# final_enclosure_wiring.net
KiCad netlist of a schematic drawn in EAGLE
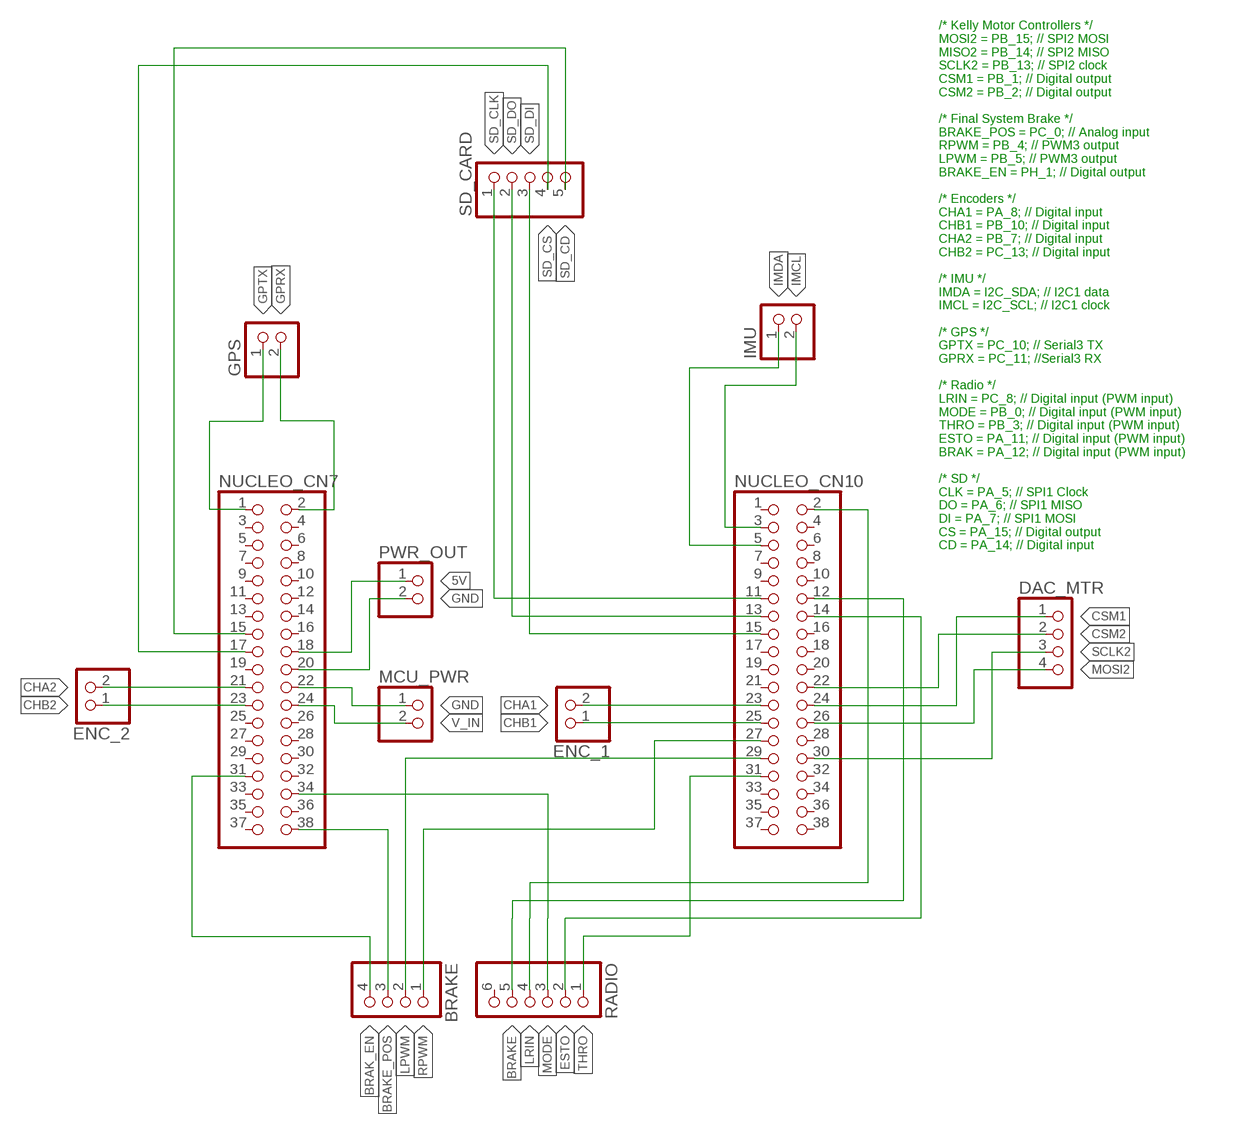
[diagram p0: schematic, sheet 1]

(export (version "E")
  (design (tool "Eeschema 10.0.6"))
  (components
    (comp (ref "BRAKE")
      (value "PINHD-1X4")
      (footprint "eagle-import:1X04")
      (libsource (lib "eagle-import") (part "PINHD-1X4"))
    )
    (comp (ref "DAC_MTR")
      (value "PINHD-1X4")
      (footprint "eagle-import:1X04")
      (libsource (lib "eagle-import") (part "PINHD-1X4"))
    )
    (comp (ref "ENC_1")
      (value "PINHD-1X2")
      (footprint "eagle-import:1X02")
      (libsource (lib "eagle-import") (part "PINHD-1X2"))
    )
    (comp (ref "ENC_2")
      (value "PINHD-1X2")
      (footprint "eagle-import:1X02")
      (libsource (lib "eagle-import") (part "PINHD-1X2"))
    )
    (comp (ref "GPS")
      (value "PINHD-1X2")
      (footprint "eagle-import:1X02")
      (libsource (lib "eagle-import") (part "PINHD-1X2"))
    )
    (comp (ref "IMU")
      (value "PINHD-1X2")
      (footprint "eagle-import:1X02")
      (libsource (lib "eagle-import") (part "PINHD-1X2"))
    )
    (comp (ref "MCU_PWR")
      (value "PINHD-1X2")
      (footprint "eagle-import:1X02")
      (libsource (lib "eagle-import") (part "PINHD-1X2"))
    )
    (comp (ref "NUCLEO_CN7")
      (value "PINHD-2X19")
      (footprint "eagle-import:2X19")
      (libsource (lib "eagle-import") (part "PINHD-2X19"))
    )
    (comp (ref "NUCLEO_CN10")
      (value "PINHD-2X19")
      (footprint "eagle-import:2X19")
      (libsource (lib "eagle-import") (part "PINHD-2X19"))
    )
    (comp (ref "PWR_OUT")
      (value "PINHD-1X2")
      (footprint "eagle-import:1X02")
      (libsource (lib "eagle-import") (part "PINHD-1X2"))
    )
    (comp (ref "RADIO")
      (value "PINHD-1X6")
      (footprint "eagle-import:1X06")
      (libsource (lib "eagle-import") (part "PINHD-1X6"))
    )
    (comp (ref "SD_CARD")
      (value "PINHD-1X5")
      (footprint "eagle-import:1X05")
      (libsource (lib "eagle-import") (part "PINHD-1X5"))
    )
  )
  (nets
    (net (code "1") (name "5V") (class "Default")
      (node (ref "NUCLEO_CN7") (pin "18") (pinfunction "18_18") (pintype "passive"))
      (node (ref "PWR_OUT") (pin "1") (pinfunction "1_1") (pintype "passive"))
    )
    (net (code "2") (name "BRAKE") (class "Default")
      (node (ref "NUCLEO_CN10") (pin "12") (pinfunction "12_12") (pintype "passive"))
      (node (ref "RADIO") (pin "5") (pinfunction "5_5") (pintype "passive"))
    )
    (net (code "3") (name "BRAKE_POS") (class "Default")
      (node (ref "BRAKE") (pin "3") (pinfunction "3_3") (pintype "passive"))
      (node (ref "NUCLEO_CN7") (pin "38") (pinfunction "38_38") (pintype "passive"))
    )
    (net (code "4") (name "BRAK_EN") (class "Default")
      (node (ref "BRAKE") (pin "4") (pinfunction "4_4") (pintype "passive"))
      (node (ref "NUCLEO_CN7") (pin "31") (pinfunction "31_31") (pintype "passive"))
    )
    (net (code "5") (name "CHA1") (class "Default")
      (node (ref "ENC_1") (pin "2") (pinfunction "2_2") (pintype "passive"))
      (node (ref "NUCLEO_CN10") (pin "23") (pinfunction "23_23") (pintype "passive"))
    )
    (net (code "6") (name "CHA2") (class "Default")
      (node (ref "ENC_2") (pin "2") (pinfunction "2_2") (pintype "passive"))
      (node (ref "NUCLEO_CN7") (pin "21") (pinfunction "21_21") (pintype "passive"))
    )
    (net (code "7") (name "CHB1") (class "Default")
      (node (ref "ENC_1") (pin "1") (pinfunction "1_1") (pintype "passive"))
      (node (ref "NUCLEO_CN10") (pin "25") (pinfunction "25_25") (pintype "passive"))
    )
    (net (code "8") (name "CHB2") (class "Default")
      (node (ref "ENC_2") (pin "1") (pinfunction "1_1") (pintype "passive"))
      (node (ref "NUCLEO_CN7") (pin "23") (pinfunction "23_23") (pintype "passive"))
    )
    (net (code "9") (name "CSM1") (class "Default")
      (node (ref "DAC_MTR") (pin "1") (pinfunction "1_1") (pintype "passive"))
      (node (ref "NUCLEO_CN10") (pin "24") (pinfunction "24_24") (pintype "passive"))
    )
    (net (code "10") (name "CSM2") (class "Default")
      (node (ref "DAC_MTR") (pin "2") (pinfunction "2_2") (pintype "passive"))
      (node (ref "NUCLEO_CN10") (pin "22") (pinfunction "22_22") (pintype "passive"))
    )
    (net (code "11") (name "ESTO") (class "Default")
      (node (ref "NUCLEO_CN10") (pin "14") (pinfunction "14_14") (pintype "passive"))
      (node (ref "RADIO") (pin "2") (pinfunction "2_2") (pintype "passive"))
    )
    (net (code "12") (name "GND") (class "Default")
      (node (ref "MCU_PWR") (pin "1") (pinfunction "1_1") (pintype "passive"))
      (node (ref "NUCLEO_CN7") (pin "20") (pinfunction "20_20") (pintype "passive"))
      (node (ref "NUCLEO_CN7") (pin "22") (pinfunction "22_22") (pintype "passive"))
      (node (ref "PWR_OUT") (pin "2") (pinfunction "2_2") (pintype "passive"))
    )
    (net (code "13") (name "GPRX") (class "Default")
      (node (ref "GPS") (pin "2") (pinfunction "2_2") (pintype "passive"))
      (node (ref "NUCLEO_CN7") (pin "2") (pinfunction "2_2") (pintype "passive"))
    )
    (net (code "14") (name "GPTX") (class "Default")
      (node (ref "GPS") (pin "1") (pinfunction "1_1") (pintype "passive"))
      (node (ref "NUCLEO_CN7") (pin "1") (pinfunction "1_1") (pintype "passive"))
    )
    (net (code "15") (name "IMCL") (class "Default")
      (node (ref "IMU") (pin "2") (pinfunction "2_2") (pintype "passive"))
      (node (ref "NUCLEO_CN10") (pin "3") (pinfunction "3_3") (pintype "passive"))
    )
    (net (code "16") (name "IMDA") (class "Default")
      (node (ref "IMU") (pin "1") (pinfunction "1_1") (pintype "passive"))
      (node (ref "NUCLEO_CN10") (pin "5") (pinfunction "5_5") (pintype "passive"))
    )
    (net (code "17") (name "LPWM") (class "Default")
      (node (ref "BRAKE") (pin "2") (pinfunction "2_2") (pintype "passive"))
      (node (ref "NUCLEO_CN10") (pin "29") (pinfunction "29_29") (pintype "passive"))
    )
    (net (code "18") (name "LRIN") (class "Default")
      (node (ref "NUCLEO_CN10") (pin "2") (pinfunction "2_2") (pintype "passive"))
      (node (ref "RADIO") (pin "4") (pinfunction "4_4") (pintype "passive"))
    )
    (net (code "19") (name "MODE") (class "Default")
      (node (ref "NUCLEO_CN7") (pin "34") (pinfunction "34_34") (pintype "passive"))
      (node (ref "RADIO") (pin "3") (pinfunction "3_3") (pintype "passive"))
    )
    (net (code "20") (name "MOSI2") (class "Default")
      (node (ref "DAC_MTR") (pin "4") (pinfunction "4_4") (pintype "passive"))
      (node (ref "NUCLEO_CN10") (pin "26") (pinfunction "26_26") (pintype "passive"))
    )
    (net (code "21") (name "RPWM") (class "Default")
      (node (ref "BRAKE") (pin "1") (pinfunction "1_1") (pintype "passive"))
      (node (ref "NUCLEO_CN10") (pin "27") (pinfunction "27_27") (pintype "passive"))
    )
    (net (code "22") (name "SCLK2") (class "Default")
      (node (ref "DAC_MTR") (pin "3") (pinfunction "3_3") (pintype "passive"))
      (node (ref "NUCLEO_CN10") (pin "30") (pinfunction "30_30") (pintype "passive"))
    )
    (net (code "23") (name "SD_CD") (class "Default")
      (node (ref "NUCLEO_CN7") (pin "15") (pinfunction "15_15") (pintype "passive"))
      (node (ref "SD_CARD") (pin "5") (pinfunction "5_5") (pintype "passive"))
    )
    (net (code "24") (name "SD_CLK") (class "Default")
      (node (ref "NUCLEO_CN10") (pin "11") (pinfunction "11_11") (pintype "passive"))
      (node (ref "SD_CARD") (pin "1") (pinfunction "1_1") (pintype "passive"))
    )
    (net (code "25") (name "SD_CS") (class "Default")
      (node (ref "NUCLEO_CN7") (pin "17") (pinfunction "17_17") (pintype "passive"))
      (node (ref "SD_CARD") (pin "4") (pinfunction "4_4") (pintype "passive"))
    )
    (net (code "26") (name "SD_DI") (class "Default")
      (node (ref "NUCLEO_CN10") (pin "15") (pinfunction "15_15") (pintype "passive"))
      (node (ref "SD_CARD") (pin "3") (pinfunction "3_3") (pintype "passive"))
    )
    (net (code "27") (name "SD_DO") (class "Default")
      (node (ref "NUCLEO_CN10") (pin "13") (pinfunction "13_13") (pintype "passive"))
      (node (ref "SD_CARD") (pin "2") (pinfunction "2_2") (pintype "passive"))
    )
    (net (code "28") (name "THRO") (class "Default")
      (node (ref "NUCLEO_CN10") (pin "31") (pinfunction "31_31") (pintype "passive"))
      (node (ref "RADIO") (pin "1") (pinfunction "1_1") (pintype "passive"))
    )
    (net (code "29") (name "V_IN") (class "Default")
      (node (ref "MCU_PWR") (pin "2") (pinfunction "2_2") (pintype "passive"))
      (node (ref "NUCLEO_CN7") (pin "24") (pinfunction "24_24") (pintype "passive"))
    )
    (net (code "30") (name "unconnected-(NUCLEO_CN7-Pad3)") (class "Default")
      (node (ref "NUCLEO_CN7") (pin "3") (pinfunction "3_3") (pintype "passive"))
    )
    (net (code "31") (name "unconnected-(NUCLEO_CN7-Pad4)") (class "Default")
      (node (ref "NUCLEO_CN7") (pin "4") (pinfunction "4_4") (pintype "passive"))
    )
    (net (code "32") (name "unconnected-(NUCLEO_CN7-Pad5)") (class "Default")
      (node (ref "NUCLEO_CN7") (pin "5") (pinfunction "5_5") (pintype "passive"))
    )
    (net (code "33") (name "unconnected-(NUCLEO_CN7-Pad6)") (class "Default")
      (node (ref "NUCLEO_CN7") (pin "6") (pinfunction "6_6") (pintype "passive"))
    )
    (net (code "34") (name "unconnected-(NUCLEO_CN7-Pad7)") (class "Default")
      (node (ref "NUCLEO_CN7") (pin "7") (pinfunction "7_7") (pintype "passive"))
    )
    (net (code "35") (name "unconnected-(NUCLEO_CN7-Pad8)") (class "Default")
      (node (ref "NUCLEO_CN7") (pin "8") (pinfunction "8_8") (pintype "passive"))
    )
    (net (code "36") (name "unconnected-(NUCLEO_CN7-Pad9)") (class "Default")
      (node (ref "NUCLEO_CN7") (pin "9") (pinfunction "9_9") (pintype "passive"))
    )
    (net (code "37") (name "unconnected-(NUCLEO_CN7-Pad10)") (class "Default")
      (node (ref "NUCLEO_CN7") (pin "10") (pinfunction "10_10") (pintype "passive"))
    )
    (net (code "38") (name "unconnected-(NUCLEO_CN7-Pad11)") (class "Default")
      (node (ref "NUCLEO_CN7") (pin "11") (pinfunction "11_11") (pintype "passive"))
    )
    (net (code "39") (name "unconnected-(NUCLEO_CN7-Pad12)") (class "Default")
      (node (ref "NUCLEO_CN7") (pin "12") (pinfunction "12_12") (pintype "passive"))
    )
    (net (code "40") (name "unconnected-(NUCLEO_CN7-Pad13)") (class "Default")
      (node (ref "NUCLEO_CN7") (pin "13") (pinfunction "13_13") (pintype "passive"))
    )
    (net (code "41") (name "unconnected-(NUCLEO_CN7-Pad14)") (class "Default")
      (node (ref "NUCLEO_CN7") (pin "14") (pinfunction "14_14") (pintype "passive"))
    )
    (net (code "42") (name "unconnected-(NUCLEO_CN7-Pad16)") (class "Default")
      (node (ref "NUCLEO_CN7") (pin "16") (pinfunction "16_16") (pintype "passive"))
    )
    (net (code "43") (name "unconnected-(NUCLEO_CN7-Pad19)") (class "Default")
      (node (ref "NUCLEO_CN7") (pin "19") (pinfunction "19_19") (pintype "passive"))
    )
    (net (code "44") (name "unconnected-(NUCLEO_CN7-Pad25)") (class "Default")
      (node (ref "NUCLEO_CN7") (pin "25") (pinfunction "25_25") (pintype "passive"))
    )
    (net (code "45") (name "unconnected-(NUCLEO_CN7-Pad26)") (class "Default")
      (node (ref "NUCLEO_CN7") (pin "26") (pinfunction "26_26") (pintype "passive"))
    )
    (net (code "46") (name "unconnected-(NUCLEO_CN7-Pad27)") (class "Default")
      (node (ref "NUCLEO_CN7") (pin "27") (pinfunction "27_27") (pintype "passive"))
    )
    (net (code "47") (name "unconnected-(NUCLEO_CN7-Pad28)") (class "Default")
      (node (ref "NUCLEO_CN7") (pin "28") (pinfunction "28_28") (pintype "passive"))
    )
    (net (code "48") (name "unconnected-(NUCLEO_CN7-Pad29)") (class "Default")
      (node (ref "NUCLEO_CN7") (pin "29") (pinfunction "29_29") (pintype "passive"))
    )
    (net (code "49") (name "unconnected-(NUCLEO_CN7-Pad30)") (class "Default")
      (node (ref "NUCLEO_CN7") (pin "30") (pinfunction "30_30") (pintype "passive"))
    )
    (net (code "50") (name "unconnected-(NUCLEO_CN7-Pad32)") (class "Default")
      (node (ref "NUCLEO_CN7") (pin "32") (pinfunction "32_32") (pintype "passive"))
    )
    (net (code "51") (name "unconnected-(NUCLEO_CN7-Pad33)") (class "Default")
      (node (ref "NUCLEO_CN7") (pin "33") (pinfunction "33_33") (pintype "passive"))
    )
    (net (code "52") (name "unconnected-(NUCLEO_CN7-Pad35)") (class "Default")
      (node (ref "NUCLEO_CN7") (pin "35") (pinfunction "35_35") (pintype "passive"))
    )
    (net (code "53") (name "unconnected-(NUCLEO_CN7-Pad36)") (class "Default")
      (node (ref "NUCLEO_CN7") (pin "36") (pinfunction "36_36") (pintype "passive"))
    )
    (net (code "54") (name "unconnected-(NUCLEO_CN7-Pad37)") (class "Default")
      (node (ref "NUCLEO_CN7") (pin "37") (pinfunction "37_37") (pintype "passive"))
    )
    (net (code "55") (name "unconnected-(NUCLEO_CN10-Pad1)") (class "Default")
      (node (ref "NUCLEO_CN10") (pin "1") (pinfunction "1_1") (pintype "passive"))
    )
    (net (code "56") (name "unconnected-(NUCLEO_CN10-Pad4)") (class "Default")
      (node (ref "NUCLEO_CN10") (pin "4") (pinfunction "4_4") (pintype "passive"))
    )
    (net (code "57") (name "unconnected-(NUCLEO_CN10-Pad6)") (class "Default")
      (node (ref "NUCLEO_CN10") (pin "6") (pinfunction "6_6") (pintype "passive"))
    )
    (net (code "58") (name "unconnected-(NUCLEO_CN10-Pad7)") (class "Default")
      (node (ref "NUCLEO_CN10") (pin "7") (pinfunction "7_7") (pintype "passive"))
    )
    (net (code "59") (name "unconnected-(NUCLEO_CN10-Pad8)") (class "Default")
      (node (ref "NUCLEO_CN10") (pin "8") (pinfunction "8_8") (pintype "passive"))
    )
    (net (code "60") (name "unconnected-(NUCLEO_CN10-Pad9)") (class "Default")
      (node (ref "NUCLEO_CN10") (pin "9") (pinfunction "9_9") (pintype "passive"))
    )
    (net (code "61") (name "unconnected-(NUCLEO_CN10-Pad10)") (class "Default")
      (node (ref "NUCLEO_CN10") (pin "10") (pinfunction "10_10") (pintype "passive"))
    )
    (net (code "62") (name "unconnected-(NUCLEO_CN10-Pad16)") (class "Default")
      (node (ref "NUCLEO_CN10") (pin "16") (pinfunction "16_16") (pintype "passive"))
    )
    (net (code "63") (name "unconnected-(NUCLEO_CN10-Pad17)") (class "Default")
      (node (ref "NUCLEO_CN10") (pin "17") (pinfunction "17_17") (pintype "passive"))
    )
    (net (code "64") (name "unconnected-(NUCLEO_CN10-Pad18)") (class "Default")
      (node (ref "NUCLEO_CN10") (pin "18") (pinfunction "18_18") (pintype "passive"))
    )
    (net (code "65") (name "unconnected-(NUCLEO_CN10-Pad19)") (class "Default")
      (node (ref "NUCLEO_CN10") (pin "19") (pinfunction "19_19") (pintype "passive"))
    )
    (net (code "66") (name "unconnected-(NUCLEO_CN10-Pad20)") (class "Default")
      (node (ref "NUCLEO_CN10") (pin "20") (pinfunction "20_20") (pintype "passive"))
    )
    (net (code "67") (name "unconnected-(NUCLEO_CN10-Pad21)") (class "Default")
      (node (ref "NUCLEO_CN10") (pin "21") (pinfunction "21_21") (pintype "passive"))
    )
    (net (code "68") (name "unconnected-(NUCLEO_CN10-Pad28)") (class "Default")
      (node (ref "NUCLEO_CN10") (pin "28") (pinfunction "28_28") (pintype "passive"))
    )
    (net (code "69") (name "unconnected-(NUCLEO_CN10-Pad32)") (class "Default")
      (node (ref "NUCLEO_CN10") (pin "32") (pinfunction "32_32") (pintype "passive"))
    )
    (net (code "70") (name "unconnected-(NUCLEO_CN10-Pad33)") (class "Default")
      (node (ref "NUCLEO_CN10") (pin "33") (pinfunction "33_33") (pintype "passive"))
    )
    (net (code "71") (name "unconnected-(NUCLEO_CN10-Pad34)") (class "Default")
      (node (ref "NUCLEO_CN10") (pin "34") (pinfunction "34_34") (pintype "passive"))
    )
    (net (code "72") (name "unconnected-(NUCLEO_CN10-Pad35)") (class "Default")
      (node (ref "NUCLEO_CN10") (pin "35") (pinfunction "35_35") (pintype "passive"))
    )
    (net (code "73") (name "unconnected-(NUCLEO_CN10-Pad36)") (class "Default")
      (node (ref "NUCLEO_CN10") (pin "36") (pinfunction "36_36") (pintype "passive"))
    )
    (net (code "74") (name "unconnected-(NUCLEO_CN10-Pad37)") (class "Default")
      (node (ref "NUCLEO_CN10") (pin "37") (pinfunction "37_37") (pintype "passive"))
    )
    (net (code "75") (name "unconnected-(NUCLEO_CN10-Pad38)") (class "Default")
      (node (ref "NUCLEO_CN10") (pin "38") (pinfunction "38_38") (pintype "passive"))
    )
    (net (code "76") (name "unconnected-(RADIO-Pad6)") (class "Default")
      (node (ref "RADIO") (pin "6") (pinfunction "6_6") (pintype "passive"))
    )
  )
)
